# 7x22_Breakout_Solar.net
KiCad netlist of a schematic drawn in EAGLE
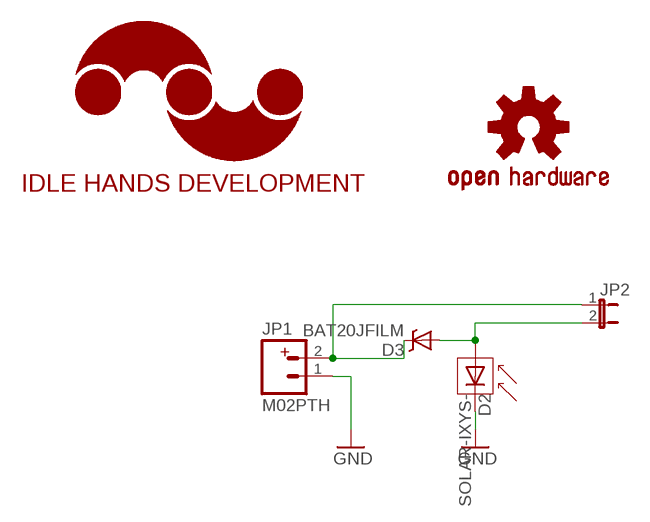
[diagram p0: schematic, sheet 1]

(export (version "E")
  (design (tool "Eeschema 10.0.6"))
  (components
    (comp (ref "D2")
      (value "SOLAR-IXYS-")
      (footprint "eagle-import:SOLARBIT-12X1")
      (libsource (lib "eagle-import") (part "SOLAR-IXYS-"))
    )
    (comp (ref "D3")
      (value "BAT20JFILM")
      (footprint "eagle-import:SOD-323")
      (libsource (lib "eagle-import") (part "BAT20JFILM"))
    )
    (comp (ref "JP1")
      (value "M02PTH")
      (footprint "eagle-import:1X02")
      (libsource (lib "eagle-import") (part "M02PTH"))
    )
    (comp (ref "JP2")
      (value "JUMPER-2SMD-NO")
      (footprint "eagle-import:SJ_2S-NO")
      (libsource (lib "eagle-import") (part "JUMPER-2SMD-NO"))
    )
    (comp (ref "LOGO1")
      (value "IDLEHANDS_LOGOS")
      (footprint "eagle-import:IHD-LOGO-S")
      (libsource (lib "eagle-import") (part "IDLEHANDS_LOGOS"))
    )
    (comp (ref "LOGO2")
      (value "OSHW-LOGOS")
      (footprint "eagle-import:OSHW-LOGO-S")
      (libsource (lib "eagle-import") (part "OSHW-LOGOS"))
    )
  )
  (nets
    (net (code "1") (name "GND") (class "Default")
      (node (ref "D2") (pin "-") (pinfunction "C_-") (pintype "passive"))
      (node (ref "JP1") (pin "1") (pinfunction "1_1") (pintype "passive"))
    )
    (net (code "2") (name "Net-(D2-A)") (class "Default")
      (node (ref "D2") (pin "+") (pinfunction "A_+") (pintype "passive"))
      (node (ref "D3") (pin "2") (pinfunction "A_2") (pintype "passive"))
      (node (ref "JP2") (pin "2") (pinfunction "2_2") (pintype "passive"))
    )
    (net (code "3") (name "Net-(D3-C)") (class "Default")
      (node (ref "D3") (pin "1") (pinfunction "C_1") (pintype "passive"))
      (node (ref "JP1") (pin "2") (pinfunction "2_2") (pintype "passive"))
      (node (ref "JP2") (pin "1") (pinfunction "1_1") (pintype "passive"))
    )
  )
)
